# 06_-_MCU.net
KiCad netlist of a schematic drawn in Altium Designer
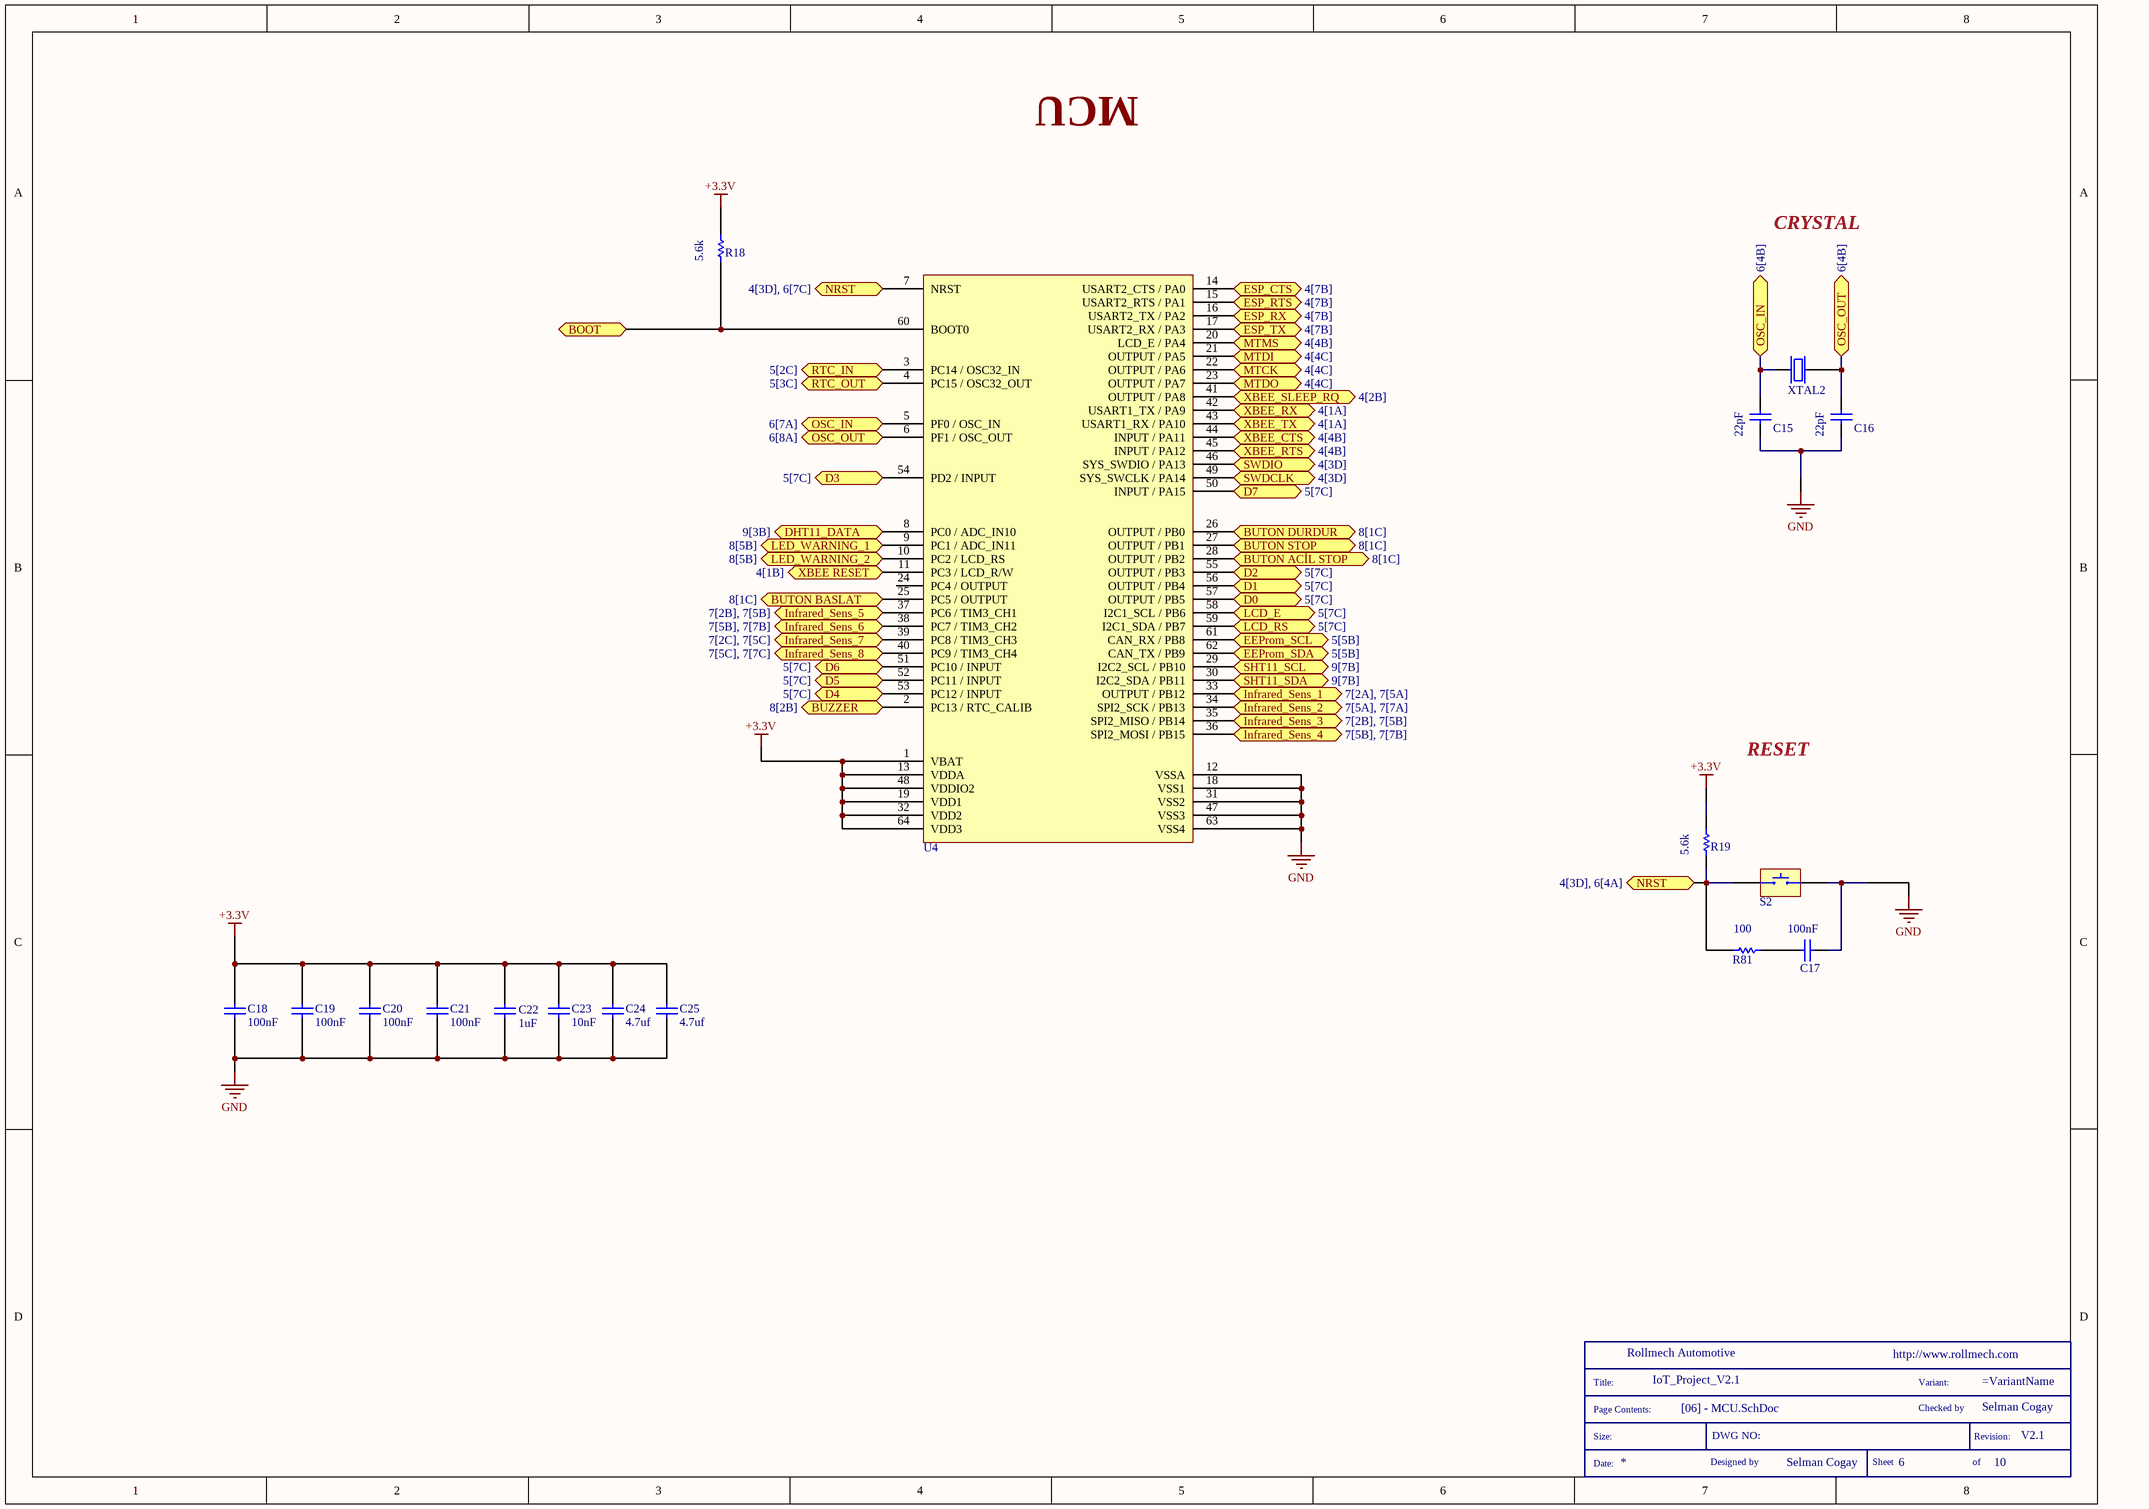
[diagram p0: [06] - MCU.SchDoc]

(export (version "E")
  (design (tool "Eeschema 10.0.6"))
  (components
    (comp (ref "C15")
      (value "22pF")
      (footprint "CAP_CER_0603")
      (description "CAP CER 22PF 100V C0G/NP0 0603")
      (libsource (lib "Rollmech_Altium") (part "GCM1885C2A220FA16D"))
    )
    (comp (ref "C16")
      (value "22pF")
      (footprint "CAP_CER_0603")
      (description "CAP CER 22PF 100V C0G/NP0 0603")
      (libsource (lib "Rollmech_Altium") (part "GCM1885C2A220FA16D"))
    )
    (comp (ref "C17")
      (value "100nF")
      (footprint "CAP_CER_0603")
      (description "CAP CER 100nf 35V X5R 0603")
      (libsource (lib "Rollmech_Altium") (part "GMK107BJ104KAHT"))
    )
    (comp (ref "C18")
      (value "100nF")
      (footprint "CAP_CER_0603")
      (description "CAP CER 100nf 35V X5R 0603")
      (libsource (lib "Rollmech_Altium") (part "GMK107BJ104KAHT"))
    )
    (comp (ref "C19")
      (value "100nF")
      (footprint "CAP_CER_0603")
      (description "CAP CER 100nf 35V X5R 0603")
      (libsource (lib "Rollmech_Altium") (part "GMK107BJ104KAHT"))
    )
    (comp (ref "C20")
      (value "100nF")
      (footprint "CAP_CER_0603")
      (description "CAP CER 100nf 35V X5R 0603")
      (libsource (lib "Rollmech_Altium") (part "GMK107BJ104KAHT"))
    )
    (comp (ref "C21")
      (value "100nF")
      (footprint "CAP_CER_0603")
      (description "CAP CER 100nf 35V X5R 0603")
      (libsource (lib "Rollmech_Altium") (part "GMK107BJ104KAHT"))
    )
    (comp (ref "C22")
      (value "1uF")
      (footprint "CAP_CER_0603")
      (description "CAP CER 1UF 35V")
      (libsource (lib "Rollmech_Altium") (part "CGA3E3X5R1V105K080AB"))
    )
    (comp (ref "C23")
      (value "10nF")
      (footprint "CAP_CER_0805")
      (description "CAP CER 10nF 100V")
      (libsource (lib "Rollmech_Altium") (part "CL21B103KC6WPNC"))
    )
    (comp (ref "C24")
      (value "4.7uf")
      (footprint "CAP_CER_0603")
      (description "CAP CER 4.7PF 50V C0G 0603")
      (libsource (lib "Rollmech_Altium") (part "CGA3E2C0G1H4R7C080AA"))
    )
    (comp (ref "C25")
      (value "4.7uf")
      (footprint "CAP_CER_0603")
      (description "CAP CER 4.7PF 50V C0G 0603")
      (libsource (lib "Rollmech_Altium") (part "CGA3E2C0G1H4R7C080AA"))
    )
    (comp (ref "R18")
      (value "5.6k")
      (footprint "RES_0805")
      (description "RES SMD 5.6K OHM 1% 1/8W 0805")
      (libsource (lib "Rollmech_Altium") (part "ERJ-6ENF5601V"))
    )
    (comp (ref "R19")
      (value "5.6k")
      (footprint "RES_0805")
      (description "RES SMD 5.6K OHM 1% 1/8W 0805")
      (libsource (lib "Rollmech_Altium") (part "ERJ-6ENF5601V"))
    )
    (comp (ref "R81")
      (value "100")
      (footprint "RES_0805")
      (description "RES SMD 100 OHM")
      (libsource (lib "Rollmech_Altium") (part "ERJ-6ENF1000V"))
    )
    (comp (ref "S2")
      (value "TAC SW")
      (footprint "TAC-SW")
      (description "SWITCH TACTILE SPST-NO 0.05A 24V")
      (libsource (lib "Rollmech_Altium") (part "FSMSMTR"))
    )
    (comp (ref "U4")
      (value "STM32F072R8T6TR")
      (footprint "LQFP64")
      (description "IC MCU 32BIT 64KB FLASH 64LQFP")
      (libsource (lib "Rollmech_Altium") (part "STM32F072R8T6TR"))
    )
    (comp (ref "XTAL2")
      (value "8Mhz")
      (footprint "HC-49/US")
      (description "CRYSTAL 8.000MHZ 18PF SMT")
      (libsource (lib "Rollmech_Altium") (part "ECS-80-18-5PLX-AGN-TR"))
    )
  )
  (nets
    (net (code "1") (name "+3.3V") (class "Default")
      (node (ref "C18") (pin "2") (pinfunction "2_2") (pintype "passive"))
      (node (ref "C19") (pin "2") (pinfunction "2_2") (pintype "passive"))
      (node (ref "C20") (pin "2") (pinfunction "2_2") (pintype "passive"))
      (node (ref "C21") (pin "2") (pinfunction "2_2") (pintype "passive"))
      (node (ref "C22") (pin "2") (pinfunction "2_2") (pintype "passive"))
      (node (ref "C23") (pin "2") (pinfunction "2_2") (pintype "passive"))
      (node (ref "C24") (pin "2") (pinfunction "2_2") (pintype "passive"))
      (node (ref "C25") (pin "2") (pinfunction "2_2") (pintype "passive"))
      (node (ref "R18") (pin "2") (pinfunction "2_2") (pintype "passive"))
      (node (ref "R19") (pin "2") (pinfunction "2_2") (pintype "passive"))
      (node (ref "U4") (pin "1") (pinfunction "VBAT_1") (pintype "passive"))
      (node (ref "U4") (pin "13") (pinfunction "VDDA_13") (pintype "passive"))
      (node (ref "U4") (pin "19") (pinfunction "VDD1_19") (pintype "passive"))
      (node (ref "U4") (pin "32") (pinfunction "VDD2_32") (pintype "passive"))
      (node (ref "U4") (pin "48") (pinfunction "VDDIO2_48") (pintype "passive"))
      (node (ref "U4") (pin "64") (pinfunction "VDD3_64") (pintype "passive"))
    )
    (net (code "2") (name "/BOOT") (class "Default")
      (node (ref "R18") (pin "1") (pinfunction "1_1") (pintype "passive"))
      (node (ref "U4") (pin "60") (pinfunction "BOOT0_60") (pintype "passive"))
    )
    (net (code "3") (name "/BUTON ACİL STOP") (class "Default")
      (node (ref "U4") (pin "28") (pinfunction "OUTPUT_/_PB2_28") (pintype "passive"))
    )
    (net (code "4") (name "/BUTON BASLAT") (class "Default")
      (node (ref "U4") (pin "25") (pinfunction "PC5_/_OUTPUT_25") (pintype "passive"))
    )
    (net (code "5") (name "/BUTON DURDUR") (class "Default")
      (node (ref "U4") (pin "26") (pinfunction "OUTPUT_/_PB0_26") (pintype "passive"))
    )
    (net (code "6") (name "/BUTON STOP") (class "Default")
      (node (ref "U4") (pin "27") (pinfunction "OUTPUT_/_PB1_27") (pintype "passive"))
    )
    (net (code "7") (name "/BUZZER") (class "Default")
      (node (ref "U4") (pin "2") (pinfunction "PC13_/_RTC_CALIB_2") (pintype "passive"))
    )
    (net (code "8") (name "/D0") (class "Default")
      (node (ref "U4") (pin "57") (pinfunction "OUTPUT_/_PB5_57") (pintype "passive"))
    )
    (net (code "9") (name "/D1") (class "Default")
      (node (ref "U4") (pin "56") (pinfunction "OUTPUT_/_PB4_56") (pintype "passive"))
    )
    (net (code "10") (name "/D2") (class "Default")
      (node (ref "U4") (pin "55") (pinfunction "OUTPUT_/_PB3_55") (pintype "passive"))
    )
    (net (code "11") (name "/D3") (class "Default")
      (node (ref "U4") (pin "54") (pinfunction "PD2_/_INPUT_54") (pintype "passive"))
    )
    (net (code "12") (name "/D4") (class "Default")
      (node (ref "U4") (pin "53") (pinfunction "PC12_/_INPUT_53") (pintype "passive"))
    )
    (net (code "13") (name "/D5") (class "Default")
      (node (ref "U4") (pin "52") (pinfunction "PC11_/_INPUT_52") (pintype "passive"))
    )
    (net (code "14") (name "/D6") (class "Default")
      (node (ref "U4") (pin "51") (pinfunction "PC10_/_INPUT_51") (pintype "passive"))
    )
    (net (code "15") (name "/D7") (class "Default")
      (node (ref "U4") (pin "50") (pinfunction "INPUT_/_PA15_50") (pintype "passive"))
    )
    (net (code "16") (name "/DHT11_DATA") (class "Default")
      (node (ref "U4") (pin "8") (pinfunction "PC0_/_ADC_IN10_8") (pintype "passive"))
    )
    (net (code "17") (name "/EEProm_SCL") (class "Default")
      (node (ref "U4") (pin "61") (pinfunction "CAN_RX_/_PB8_61") (pintype "passive"))
    )
    (net (code "18") (name "/EEProm_SDA") (class "Default")
      (node (ref "U4") (pin "62") (pinfunction "CAN_TX_/_PB9_62") (pintype "passive"))
    )
    (net (code "19") (name "/ESP_CTS") (class "Default")
      (node (ref "U4") (pin "14") (pinfunction "USART2_CTS_/_PA0_14") (pintype "passive"))
    )
    (net (code "20") (name "/ESP_RTS") (class "Default")
      (node (ref "U4") (pin "15") (pinfunction "USART2_RTS_/_PA1_15") (pintype "passive"))
    )
    (net (code "21") (name "/ESP_RX") (class "Default")
      (node (ref "U4") (pin "16") (pinfunction "USART2_TX_/_PA2_16") (pintype "passive"))
    )
    (net (code "22") (name "/ESP_TX") (class "Default")
      (node (ref "U4") (pin "17") (pinfunction "USART2_RX_/_PA3_17") (pintype "passive"))
    )
    (net (code "23") (name "/Infrared_Sens_1") (class "Default")
      (node (ref "U4") (pin "33") (pinfunction "OUTPUT_/_PB12_33") (pintype "passive"))
    )
    (net (code "24") (name "/Infrared_Sens_2") (class "Default")
      (node (ref "U4") (pin "34") (pinfunction "SPI2_SCK_/_PB13_34") (pintype "passive"))
    )
    (net (code "25") (name "/Infrared_Sens_3") (class "Default")
      (node (ref "U4") (pin "35") (pinfunction "SPI2_MISO_/_PB14_35") (pintype "passive"))
    )
    (net (code "26") (name "/Infrared_Sens_4") (class "Default")
      (node (ref "U4") (pin "36") (pinfunction "SPI2_MOSI_/_PB15_36") (pintype "passive"))
    )
    (net (code "27") (name "/Infrared_Sens_5") (class "Default")
      (node (ref "U4") (pin "37") (pinfunction "PC6_/_TIM3_CH1_37") (pintype "passive"))
    )
    (net (code "28") (name "/Infrared_Sens_6") (class "Default")
      (node (ref "U4") (pin "38") (pinfunction "PC7_/_TIM3_CH2_38") (pintype "passive"))
    )
    (net (code "29") (name "/Infrared_Sens_7") (class "Default")
      (node (ref "U4") (pin "39") (pinfunction "PC8_/_TIM3_CH3_39") (pintype "passive"))
    )
    (net (code "30") (name "/Infrared_Sens_8") (class "Default")
      (node (ref "U4") (pin "40") (pinfunction "PC9_/_TIM3_CH4_40") (pintype "passive"))
    )
    (net (code "31") (name "/LCD_E") (class "Default")
      (node (ref "U4") (pin "58") (pinfunction "I2C1_SCL_/_PB6_58") (pintype "passive"))
    )
    (net (code "32") (name "/LCD_RS") (class "Default")
      (node (ref "U4") (pin "59") (pinfunction "I2C1_SDA_/_PB7_59") (pintype "passive"))
    )
    (net (code "33") (name "/LED_WARNING_1") (class "Default")
      (node (ref "U4") (pin "9") (pinfunction "PC1_/_ADC_IN11_9") (pintype "passive"))
    )
    (net (code "34") (name "/LED_WARNING_2") (class "Default")
      (node (ref "U4") (pin "10") (pinfunction "PC2_/_LCD_RS_10") (pintype "passive"))
    )
    (net (code "35") (name "/MTCK") (class "Default")
      (node (ref "U4") (pin "22") (pinfunction "OUTPUT_/_PA6_22") (pintype "passive"))
    )
    (net (code "36") (name "/MTDI") (class "Default")
      (node (ref "U4") (pin "21") (pinfunction "OUTPUT_/_PA5_21") (pintype "passive"))
    )
    (net (code "37") (name "/MTDO") (class "Default")
      (node (ref "U4") (pin "23") (pinfunction "OUTPUT_/_PA7_23") (pintype "passive"))
    )
    (net (code "38") (name "/MTMS") (class "Default")
      (node (ref "U4") (pin "20") (pinfunction "LCD_E_/_PA4_20") (pintype "passive"))
    )
    (net (code "39") (name "/NRST") (class "Default")
      (node (ref "R19") (pin "1") (pinfunction "1_1") (pintype "passive"))
      (node (ref "R81") (pin "1") (pinfunction "1_1") (pintype "passive"))
      (node (ref "S2") (pin "1") (pinfunction "1_1") (pintype "passive"))
      (node (ref "U4") (pin "7") (pinfunction "NRST_7") (pintype "passive"))
    )
    (net (code "40") (name "/OSC_IN") (class "Default")
      (node (ref "C15") (pin "2") (pinfunction "2_2") (pintype "passive"))
      (node (ref "U4") (pin "5") (pinfunction "PF0_/_OSC_IN_5") (pintype "passive"))
      (node (ref "XTAL2") (pin "1") (pinfunction "1_1") (pintype "passive"))
    )
    (net (code "41") (name "/OSC_OUT") (class "Default")
      (node (ref "C16") (pin "2") (pinfunction "2_2") (pintype "passive"))
      (node (ref "U4") (pin "6") (pinfunction "PF1_/_OSC_OUT_6") (pintype "passive"))
      (node (ref "XTAL2") (pin "2") (pinfunction "2_2") (pintype "passive"))
    )
    (net (code "42") (name "/RTC_IN") (class "Default")
      (node (ref "U4") (pin "3") (pinfunction "PC14_/_OSC32_IN_3") (pintype "passive"))
    )
    (net (code "43") (name "/RTC_OUT") (class "Default")
      (node (ref "U4") (pin "4") (pinfunction "PC15_/_OSC32_OUT_4") (pintype "passive"))
    )
    (net (code "44") (name "/SHT11_SCL") (class "Default")
      (node (ref "U4") (pin "29") (pinfunction "I2C2_SCL_/_PB10_29") (pintype "passive"))
    )
    (net (code "45") (name "/SHT11_SDA") (class "Default")
      (node (ref "U4") (pin "30") (pinfunction "I2C2_SDA_/_PB11_30") (pintype "passive"))
    )
    (net (code "46") (name "/SWDCLK") (class "Default")
      (node (ref "U4") (pin "49") (pinfunction "SYS_SWCLK_/_PA14_49") (pintype "passive"))
    )
    (net (code "47") (name "/SWDIO") (class "Default")
      (node (ref "U4") (pin "46") (pinfunction "SYS_SWDIO_/_PA13_46") (pintype "passive"))
    )
    (net (code "48") (name "/XBEE RESET") (class "Default")
      (node (ref "U4") (pin "11") (pinfunction "PC3_/_LCD_R/W_11") (pintype "passive"))
    )
    (net (code "49") (name "/XBEE_CTS") (class "Default")
      (node (ref "U4") (pin "44") (pinfunction "INPUT_/_PA11_44") (pintype "passive"))
    )
    (net (code "50") (name "/XBEE_RTS") (class "Default")
      (node (ref "U4") (pin "45") (pinfunction "INPUT_/_PA12_45") (pintype "passive"))
    )
    (net (code "51") (name "/XBEE_RX") (class "Default")
      (node (ref "U4") (pin "42") (pinfunction "USART1_TX_/_PA9_42") (pintype "passive"))
    )
    (net (code "52") (name "/XBEE_SLEEP_RQ") (class "Default")
      (node (ref "U4") (pin "41") (pinfunction "OUTPUT_/_PA8_41") (pintype "passive"))
    )
    (net (code "53") (name "/XBEE_TX") (class "Default")
      (node (ref "U4") (pin "43") (pinfunction "USART1_RX_/_PA10_43") (pintype "passive"))
    )
    (net (code "54") (name "GND") (class "Default")
      (node (ref "C15") (pin "1") (pinfunction "1_1") (pintype "passive"))
      (node (ref "C16") (pin "1") (pinfunction "1_1") (pintype "passive"))
      (node (ref "C17") (pin "2") (pinfunction "2_2") (pintype "passive"))
      (node (ref "C18") (pin "1") (pinfunction "1_1") (pintype "passive"))
      (node (ref "C19") (pin "1") (pinfunction "1_1") (pintype "passive"))
      (node (ref "C20") (pin "1") (pinfunction "1_1") (pintype "passive"))
      (node (ref "C21") (pin "1") (pinfunction "1_1") (pintype "passive"))
      (node (ref "C22") (pin "1") (pinfunction "1_1") (pintype "passive"))
      (node (ref "C23") (pin "1") (pinfunction "1_1") (pintype "passive"))
      (node (ref "C24") (pin "1") (pinfunction "1_1") (pintype "passive"))
      (node (ref "C25") (pin "1") (pinfunction "1_1") (pintype "passive"))
      (node (ref "S2") (pin "2") (pinfunction "2_2") (pintype "passive"))
      (node (ref "U4") (pin "12") (pinfunction "VSSA_12") (pintype "passive"))
      (node (ref "U4") (pin "18") (pinfunction "VSS1_18") (pintype "passive"))
      (node (ref "U4") (pin "31") (pinfunction "VSS2_31") (pintype "passive"))
      (node (ref "U4") (pin "47") (pinfunction "VSS3_47") (pintype "passive"))
      (node (ref "U4") (pin "63") (pinfunction "VSS4_63") (pintype "passive"))
    )
    (net (code "55") (name "Net-(C17-Pad1)") (class "Default")
      (node (ref "C17") (pin "1") (pinfunction "1_1") (pintype "passive"))
      (node (ref "R81") (pin "2") (pinfunction "2_2") (pintype "passive"))
    )
    (net (code "56") (name "unconnected-(U4-PC4_{slash}_OUTPUT-Pad24)") (class "Default")
      (node (ref "U4") (pin "24") (pinfunction "PC4_/_OUTPUT_24") (pintype "passive"))
    )
  )
)
